# serializer.net
KiCad netlist of a schematic drawn in EAGLE
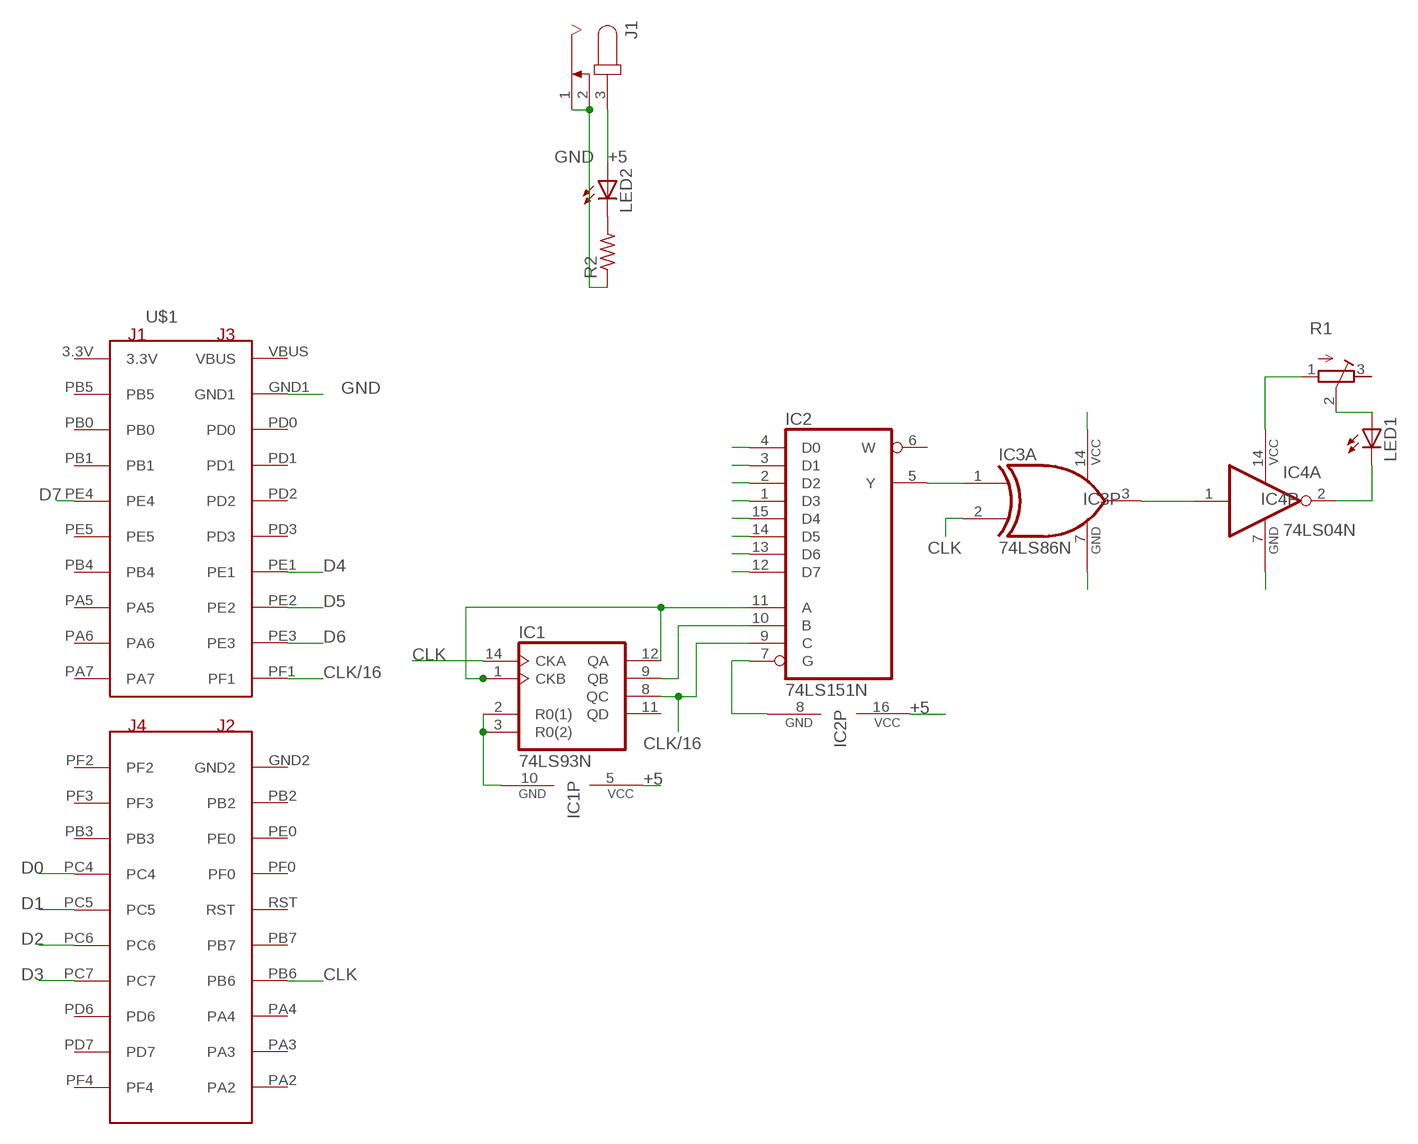
[diagram p0: schematic, sheet 1]

(export (version "E")
  (design (tool "Eeschema 10.0.6"))
  (components
    (comp (ref "IC1")
      (value "74LS93N")
      (footprint "eagle-import:DIL14")
      (libsource (lib "eagle-import") (part "7493NLS"))
    )
    (comp (ref "IC2")
      (value "74LS151N")
      (footprint "eagle-import:DIL16")
      (libsource (lib "eagle-import") (part "74151NLS"))
    )
    (comp (ref "IC3")
      (value "74LS86N")
      (footprint "eagle-import:DIL14")
      (libsource (lib "eagle-import") (part "7486NLS"))
    )
    (comp (ref "IC4")
      (value "74LS04N")
      (footprint "eagle-import:DIL14")
      (libsource (lib "eagle-import") (part "7404NLS"))
    )
    (comp (ref "J1")
      (value "JACK-PLUG0")
      (footprint "eagle-import:SPC4077")
      (libsource (lib "eagle-import") (part "JACK-PLUG0"))
    )
    (comp (ref "LED1")
      (value "LED5MM")
      (footprint "eagle-import:LED5MM")
      (libsource (lib "eagle-import") (part "LED5MM"))
    )
    (comp (ref "LED2")
      (value "LED5MM")
      (footprint "eagle-import:LED5MM")
      (libsource (lib "eagle-import") (part "LED5MM"))
    )
    (comp (ref "R1")
      (value "R-TRIMM3296Y")
      (footprint "eagle-import:RTRIM3296Y")
      (libsource (lib "eagle-import") (part "R-TRIMM3296Y"))
    )
    (comp (ref "R2")
      (value "R-US_0207/10")
      (footprint "eagle-import:0207_10")
      (libsource (lib "eagle-import") (part "R-US_0207/10"))
    )
    (comp (ref "U$1")
      (value "STELLARIS_LAUNCHPAD_BLIZZARD_XL_HEADERS")
      (footprint "eagle-import:STELLARISLAUNCHPADHEADERS")
      (libsource (lib "eagle-import") (part "STELLARIS_LAUNCHPAD_BLIZZARD_XL_HEADERS"))
    )
  )
  (nets
    (net (code "1") (name "/+5") (class "Default")
      (node (ref "IC1") (pin "5") (pinfunction "VCC_5") (pintype "power_in"))
      (node (ref "IC2") (pin "16") (pinfunction "VCC_16") (pintype "power_in"))
      (node (ref "IC3") (pin "14") (pinfunction "VCC_14") (pintype "power_in"))
      (node (ref "IC4") (pin "14") (pinfunction "VCC_14") (pintype "power_in"))
      (node (ref "J1") (pin "3") (pinfunction "3_3") (pintype "passive"))
      (node (ref "LED2") (pin "A") (pinfunction "A_A") (pintype "passive"))
      (node (ref "R1") (pin "1") (pinfunction "A_1") (pintype "passive"))
    )
    (net (code "2") (name "/3.3V") (class "Default")
      (node (ref "U$1") (pin "3.3V") (pinfunction "3.3V_3.3V") (pintype "power_in"))
    )
    (net (code "3") (name "/CLK") (class "Default")
      (node (ref "IC1") (pin "14") (pinfunction "CKA_14") (pintype "input"))
      (node (ref "IC3") (pin "2") (pinfunction "I1_2") (pintype "input"))
      (node (ref "U$1") (pin "PB6") (pinfunction "PB6_PB6") (pintype "bidirectional"))
    )
    (net (code "4") (name "/CLK{slash}16") (class "Default")
      (node (ref "IC1") (pin "8") (pinfunction "QC_8") (pintype "output"))
      (node (ref "IC2") (pin "9") (pinfunction "C_9") (pintype "input"))
      (node (ref "U$1") (pin "PF1") (pinfunction "PF1_PF1") (pintype "bidirectional"))
    )
    (net (code "5") (name "/D0") (class "Default")
      (node (ref "IC2") (pin "4") (pinfunction "D0_4") (pintype "input"))
      (node (ref "U$1") (pin "PC4") (pinfunction "PC4_PC4") (pintype "bidirectional"))
    )
    (net (code "6") (name "/D1") (class "Default")
      (node (ref "IC2") (pin "3") (pinfunction "D1_3") (pintype "input"))
      (node (ref "U$1") (pin "PC5") (pinfunction "PC5_PC5") (pintype "bidirectional"))
    )
    (net (code "7") (name "/D2") (class "Default")
      (node (ref "IC2") (pin "2") (pinfunction "D2_2") (pintype "input"))
      (node (ref "U$1") (pin "PC6") (pinfunction "PC6_PC6") (pintype "bidirectional"))
    )
    (net (code "8") (name "/D3") (class "Default")
      (node (ref "IC2") (pin "1") (pinfunction "D3_1") (pintype "input"))
      (node (ref "U$1") (pin "PC7") (pinfunction "PC7_PC7") (pintype "bidirectional"))
    )
    (net (code "9") (name "/D4") (class "Default")
      (node (ref "IC2") (pin "15") (pinfunction "D4_15") (pintype "input"))
      (node (ref "U$1") (pin "PE1") (pinfunction "PE1_PE1") (pintype "bidirectional"))
    )
    (net (code "10") (name "/D5") (class "Default")
      (node (ref "IC2") (pin "14") (pinfunction "D5_14") (pintype "input"))
      (node (ref "U$1") (pin "PE2") (pinfunction "PE2_PE2") (pintype "bidirectional"))
    )
    (net (code "11") (name "/D6") (class "Default")
      (node (ref "IC2") (pin "13") (pinfunction "D6_13") (pintype "input"))
      (node (ref "U$1") (pin "PE3") (pinfunction "PE3_PE3") (pintype "bidirectional"))
    )
    (net (code "12") (name "/D7") (class "Default")
      (node (ref "IC2") (pin "12") (pinfunction "D7_12") (pintype "input"))
      (node (ref "U$1") (pin "PE4") (pinfunction "PE4_PE4") (pintype "bidirectional"))
    )
    (net (code "13") (name "/GND") (class "Default")
      (node (ref "IC1") (pin "10") (pinfunction "GND_10") (pintype "power_in"))
      (node (ref "IC1") (pin "2") (pinfunction "R0(1)_2") (pintype "input"))
      (node (ref "IC1") (pin "3") (pinfunction "R0(2)_3") (pintype "input"))
      (node (ref "IC2") (pin "7") (pinfunction "G_7") (pintype "input"))
      (node (ref "IC2") (pin "8") (pinfunction "GND_8") (pintype "power_in"))
      (node (ref "IC3") (pin "7") (pinfunction "GND_7") (pintype "power_in"))
      (node (ref "IC4") (pin "7") (pinfunction "GND_7") (pintype "power_in"))
      (node (ref "J1") (pin "1") (pinfunction "1_1") (pintype "passive"))
      (node (ref "J1") (pin "2") (pinfunction "2_2") (pintype "passive"))
      (node (ref "R2") (pin "1") (pinfunction "1_1") (pintype "passive"))
      (node (ref "U$1") (pin "GND1") (pinfunction "GND1_GND1") (pintype "bidirectional"))
    )
    (net (code "14") (name "/GND2") (class "Default")
      (node (ref "U$1") (pin "GND2") (pinfunction "GND2_GND2") (pintype "power_in"))
    )
    (net (code "15") (name "/RST") (class "Default")
      (node (ref "U$1") (pin "RST") (pinfunction "RST_RST") (pintype "power_in"))
    )
    (net (code "16") (name "/VBUS") (class "Default")
      (node (ref "U$1") (pin "VBUS") (pinfunction "VBUS_VBUS") (pintype "power_in"))
    )
    (net (code "17") (name "Net-(IC1A-CKB)") (class "Default")
      (node (ref "IC1") (pin "1") (pinfunction "CKB_1") (pintype "input"))
      (node (ref "IC1") (pin "12") (pinfunction "QA_12") (pintype "output"))
      (node (ref "IC2") (pin "11") (pinfunction "A_11") (pintype "input"))
    )
    (net (code "18") (name "Net-(IC1A-QB)") (class "Default")
      (node (ref "IC1") (pin "9") (pinfunction "QB_9") (pintype "output"))
      (node (ref "IC2") (pin "10") (pinfunction "B_10") (pintype "input"))
    )
    (net (code "19") (name "Net-(IC2A-Y)") (class "Default")
      (node (ref "IC2") (pin "5") (pinfunction "Y_5") (pintype "output"))
      (node (ref "IC3") (pin "1") (pinfunction "I0_1") (pintype "input"))
    )
    (net (code "20") (name "Net-(IC3A-O)") (class "Default")
      (node (ref "IC3") (pin "3") (pinfunction "O_3") (pintype "output"))
      (node (ref "IC4") (pin "1") (pinfunction "I_1") (pintype "input"))
    )
    (net (code "21") (name "Net-(IC4A-O)") (class "Default")
      (node (ref "IC4") (pin "2") (pinfunction "O_2") (pintype "output"))
      (node (ref "LED1") (pin "K") (pinfunction "C_K") (pintype "passive"))
    )
    (net (code "22") (name "Net-(LED2-C)") (class "Default")
      (node (ref "LED2") (pin "K") (pinfunction "C_K") (pintype "passive"))
      (node (ref "R2") (pin "2") (pinfunction "2_2") (pintype "passive"))
    )
    (net (code "23") (name "Net-(R1-S)") (class "Default")
      (node (ref "LED1") (pin "A") (pinfunction "A_A") (pintype "passive"))
      (node (ref "R1") (pin "2") (pinfunction "S_2") (pintype "passive"))
    )
    (net (code "24") (name "unconnected-(IC1A-QD-Pad11)") (class "Default")
      (node (ref "IC1") (pin "11") (pinfunction "QD_11") (pintype "output"))
    )
    (net (code "25") (name "unconnected-(IC2A-W-Pad6)") (class "Default")
      (node (ref "IC2") (pin "6") (pinfunction "W_6") (pintype "output"))
    )
    (net (code "26") (name "unconnected-(R1-E-Pad3)") (class "Default")
      (node (ref "R1") (pin "3") (pinfunction "E_3") (pintype "passive"))
    )
    (net (code "27") (name "unconnected-(U$1-PadPA2)") (class "Default")
      (node (ref "U$1") (pin "PA2") (pinfunction "PA2_PA2") (pintype "bidirectional"))
    )
    (net (code "28") (name "unconnected-(U$1-PadPA3)") (class "Default")
      (node (ref "U$1") (pin "PA3") (pinfunction "PA3_PA3") (pintype "bidirectional"))
    )
    (net (code "29") (name "unconnected-(U$1-PadPA4)") (class "Default")
      (node (ref "U$1") (pin "PA4") (pinfunction "PA4_PA4") (pintype "bidirectional"))
    )
    (net (code "30") (name "unconnected-(U$1-PadPA5)") (class "Default")
      (node (ref "U$1") (pin "PA5") (pinfunction "PA5_PA5") (pintype "bidirectional"))
    )
    (net (code "31") (name "unconnected-(U$1-PadPA6)") (class "Default")
      (node (ref "U$1") (pin "PA6") (pinfunction "PA6_PA6") (pintype "bidirectional"))
    )
    (net (code "32") (name "unconnected-(U$1-PadPA7)") (class "Default")
      (node (ref "U$1") (pin "PA7") (pinfunction "PA7_PA7") (pintype "bidirectional"))
    )
    (net (code "33") (name "unconnected-(U$1-PadPB0)") (class "Default")
      (node (ref "U$1") (pin "PB0") (pinfunction "PB0_PB0") (pintype "bidirectional"))
    )
    (net (code "34") (name "unconnected-(U$1-PadPB1)") (class "Default")
      (node (ref "U$1") (pin "PB1") (pinfunction "PB1_PB1") (pintype "bidirectional"))
    )
    (net (code "35") (name "unconnected-(U$1-PadPB2)") (class "Default")
      (node (ref "U$1") (pin "PB2") (pinfunction "PB2_PB2") (pintype "bidirectional"))
    )
    (net (code "36") (name "unconnected-(U$1-PadPB3)") (class "Default")
      (node (ref "U$1") (pin "PB3") (pinfunction "PB3_PB3") (pintype "bidirectional"))
    )
    (net (code "37") (name "unconnected-(U$1-PadPB4)") (class "Default")
      (node (ref "U$1") (pin "PB4") (pinfunction "PB4_PB4") (pintype "bidirectional"))
    )
    (net (code "38") (name "unconnected-(U$1-PadPB5)") (class "Default")
      (node (ref "U$1") (pin "PB5") (pinfunction "PB5_PB5") (pintype "bidirectional"))
    )
    (net (code "39") (name "unconnected-(U$1-PadPB7)") (class "Default")
      (node (ref "U$1") (pin "PB7") (pinfunction "PB7_PB7") (pintype "bidirectional"))
    )
    (net (code "40") (name "unconnected-(U$1-PadPD0)") (class "Default")
      (node (ref "U$1") (pin "PD0") (pinfunction "PD0_PD0") (pintype "bidirectional"))
    )
    (net (code "41") (name "unconnected-(U$1-PadPD1)") (class "Default")
      (node (ref "U$1") (pin "PD1") (pinfunction "PD1_PD1") (pintype "bidirectional"))
    )
    (net (code "42") (name "unconnected-(U$1-PadPD2)") (class "Default")
      (node (ref "U$1") (pin "PD2") (pinfunction "PD2_PD2") (pintype "bidirectional"))
    )
    (net (code "43") (name "unconnected-(U$1-PadPD3)") (class "Default")
      (node (ref "U$1") (pin "PD3") (pinfunction "PD3_PD3") (pintype "bidirectional"))
    )
    (net (code "44") (name "unconnected-(U$1-PadPD6)") (class "Default")
      (node (ref "U$1") (pin "PD6") (pinfunction "PD6_PD6") (pintype "bidirectional"))
    )
    (net (code "45") (name "unconnected-(U$1-PadPD7)") (class "Default")
      (node (ref "U$1") (pin "PD7") (pinfunction "PD7_PD7") (pintype "bidirectional"))
    )
    (net (code "46") (name "unconnected-(U$1-PadPE0)") (class "Default")
      (node (ref "U$1") (pin "PE0") (pinfunction "PE0_PE0") (pintype "bidirectional"))
    )
    (net (code "47") (name "unconnected-(U$1-PadPE5)") (class "Default")
      (node (ref "U$1") (pin "PE5") (pinfunction "PE5_PE5") (pintype "bidirectional"))
    )
    (net (code "48") (name "unconnected-(U$1-PadPF0)") (class "Default")
      (node (ref "U$1") (pin "PF0") (pinfunction "PF0_PF0") (pintype "bidirectional"))
    )
    (net (code "49") (name "unconnected-(U$1-PadPF2)") (class "Default")
      (node (ref "U$1") (pin "PF2") (pinfunction "PF2_PF2") (pintype "bidirectional"))
    )
    (net (code "50") (name "unconnected-(U$1-PadPF3)") (class "Default")
      (node (ref "U$1") (pin "PF3") (pinfunction "PF3_PF3") (pintype "bidirectional"))
    )
    (net (code "51") (name "unconnected-(U$1-PadPF4)") (class "Default")
      (node (ref "U$1") (pin "PF4") (pinfunction "PF4_PF4") (pintype "bidirectional"))
    )
  )
)
